# ESC.net
KiCad netlist of a schematic drawn in Altium Designer
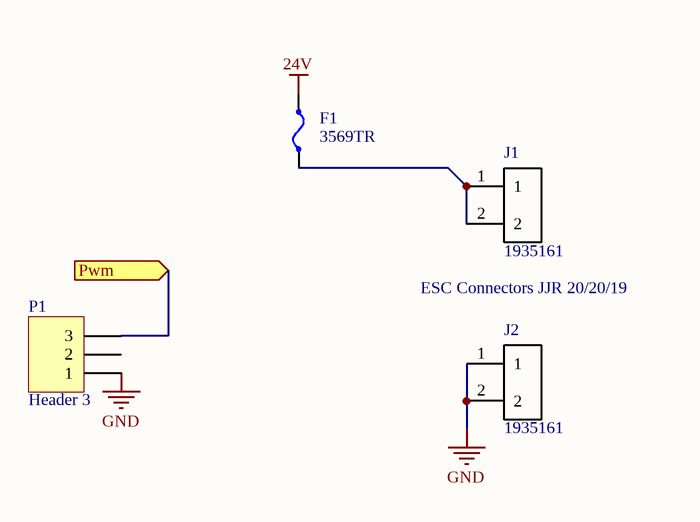
[diagram p0: ESC.SchDoc]

(export (version "E")
  (design (tool "Eeschema 10.0.6"))
  (components
    (comp (ref "F1")
      (value "3569TR")
      (footprint "Horizontal SMD fuse clip")
      (description "Fuse Clip Assembly")
      (fields (field (name "MANUFACTURER PART NUMBER") "3569TR"))
      (libsource (lib "Keystone SchLib") (part "3569TR"))
    )
    (comp (ref "J1")
      (value "1935161")
      (footprint "PHOENIX_1935161")
      (description "Conn Terminal Blocks 2 POS 5mm Solder ST Thru-Hole 16A")
      (fields (field (name "MF") "Phoenix Contact"))
      (libsource (lib "URC_Lib") (part "1935161"))
    )
    (comp (ref "J2")
      (value "1935161")
      (footprint "PHOENIX_1935161")
      (description "Conn Terminal Blocks 2 POS 5mm Solder ST Thru-Hole 16A")
      (fields (field (name "MF") "Phoenix Contact"))
      (libsource (lib "URC_Lib") (part "1935161"))
    )
    (comp (ref "P1")
      (value "Header 3")
      (footprint "HDR1X3")
      (description "Header, 3-Pin")
      (fields (field (name "PUBLISHER") "Altium Limited"))
      (libsource (lib "Miscellaneous Connectors") (part "Header 3"))
    )
  )
  (nets
    (net (code "1") (name "/Pwm") (class "Default")
      (node (ref "P1") (pin "3") (pinfunction "3_3") (pintype "passive"))
    )
    (net (code "2") (name "24V") (class "Default")
      (node (ref "F1") (pin "1") (pinfunction "1_1") (pintype "passive"))
    )
    (net (code "3") (name "GND") (class "Default")
      (node (ref "J2") (pin "1") (pinfunction "1_1") (pintype "passive"))
      (node (ref "J2") (pin "2") (pinfunction "2_2") (pintype "passive"))
      (node (ref "P1") (pin "1") (pinfunction "1_1") (pintype "passive"))
    )
    (net (code "4") (name "Net-(F1-Pad2)") (class "Default")
      (node (ref "F1") (pin "2") (pinfunction "2_2") (pintype "passive"))
      (node (ref "J1") (pin "1") (pinfunction "1_1") (pintype "passive"))
      (node (ref "J1") (pin "2") (pinfunction "2_2") (pintype "passive"))
    )
    (net (code "5") (name "unconnected-(P1-Pad2)") (class "Default")
      (node (ref "P1") (pin "2") (pinfunction "2_2") (pintype "passive"))
    )
  )
)
